# Power.net
KiCad netlist of a schematic drawn in Altium Designer
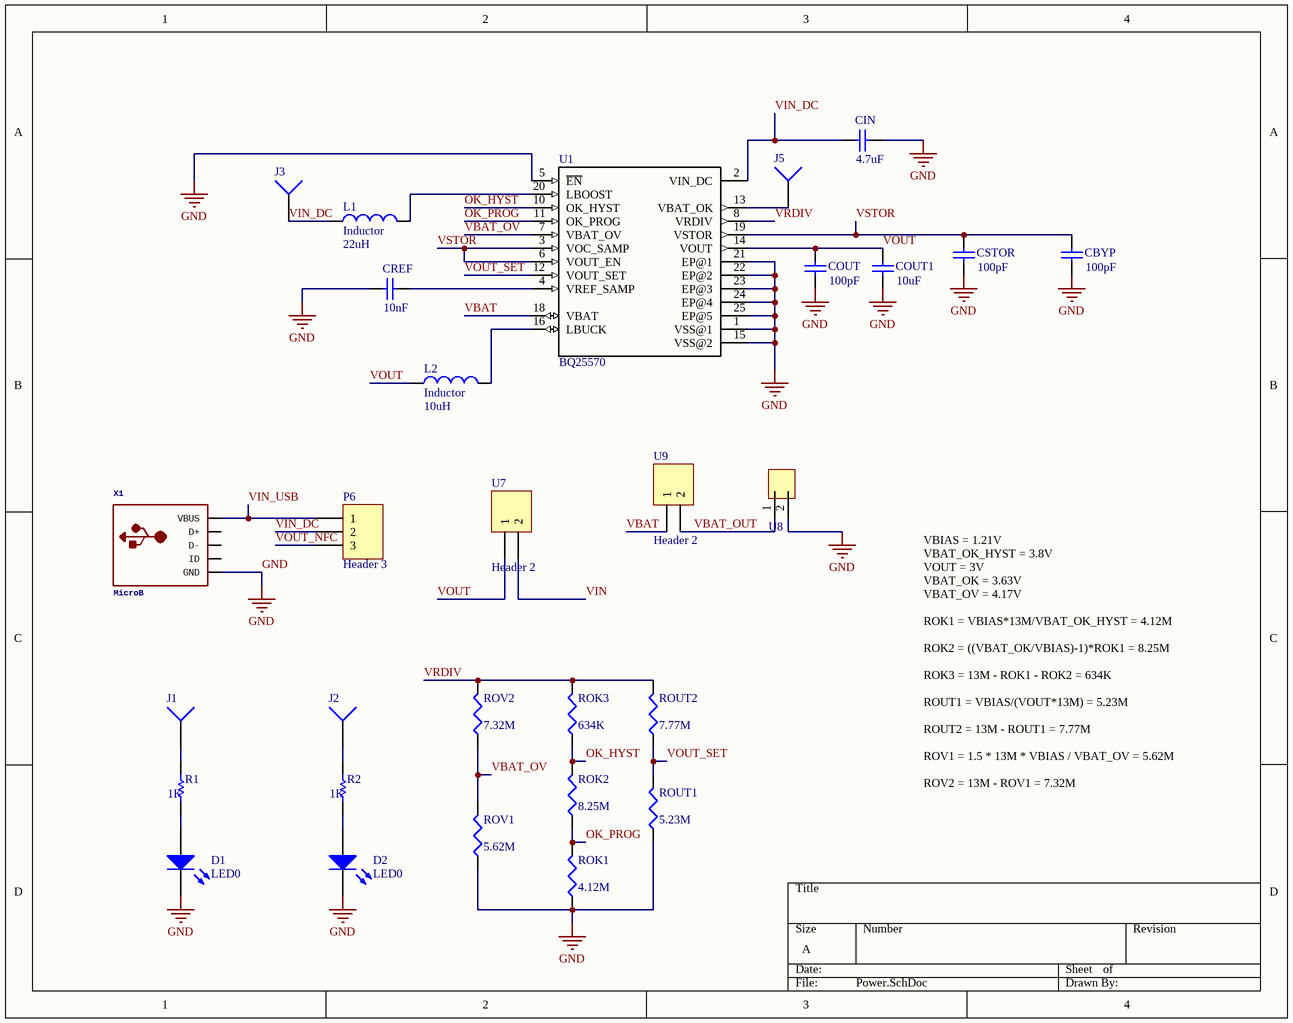
[diagram p0: Power.SchDoc]

(export (version "E")
  (design (tool "Eeschema 10.0.6"))
  (components
    (comp (ref "CBYP")
      (value "100pF")
      (footprint "C1206")
      (description "CAP CER 100PF 50V C0G/NPO 0603")
      (fields (field (name "DIGI-KEY PART NUMBER") "311-1069-1-ND") (field (name "MANUFACTURER") "Yageo"))
      (libsource (lib "Miscellaneous Devices") (part "Cap Semi"))
    )
    (comp (ref "CIN")
      (value "4.7uF")
      (footprint "C1206")
      (description "CAP CER 4.7UF 10V X5R 0603")
      (fields
        (field (name "DIGI-KEY PART NUMBER") "1276-6684-1-ND")
        (field (name "MANUFACTURER") "Samsung Electro-Mechanics")
      )
      (libsource (lib "Miscellaneous Devices") (part "Cap Semi"))
    )
    (comp (ref "COUT")
      (value "100pF")
      (footprint "C1206")
      (description "CAP CER 100PF 50V C0G/NPO 0603")
      (fields (field (name "DIGI-KEY PART NUMBER") "311-1069-1-ND") (field (name "MANUFACTURER") "Yageo"))
      (libsource (lib "Miscellaneous Devices") (part "Cap Semi"))
    )
    (comp (ref "COUT1")
      (value "10uF")
      (footprint "C1206")
      (description "CL10A106MQ8NNNC")
      (fields
        (field (name "DIGI-KEY PART NUMBER") "1276-1119-1-ND")
        (field (name "MANUFACTURER") "Samsung Electro-Mechanics")
      )
      (libsource (lib "Miscellaneous Devices") (part "Cap Semi"))
    )
    (comp (ref "CREF")
      (value "10nF")
      (footprint "C1206")
      (description "CAP CER 10000PF 100V X7R 0603")
      (fields
        (field (name "DIGI-KEY PART NUMBER") "445-1305-1-ND")
        (field (name "MANUFACTURER") "TDK Corporation")
      )
      (libsource (lib "Miscellaneous Devices") (part "Cap Semi"))
    )
    (comp (ref "CSTOR")
      (value "100pF")
      (footprint "C1206")
      (description "CAP CER 100PF 50V C0G/NPO 0603")
      (fields (field (name "DIGI-KEY PART NUMBER") "311-1069-1-ND") (field (name "MANUFACTURER") "Yageo"))
      (libsource (lib "Miscellaneous Devices") (part "Cap Semi"))
    )
    (comp (ref "D1")
      (value "LED0")
      (footprint "LED-0")
      (description "LED BLUE CLEAR CHIP SMD")
      (fields
        (field (name "DIGI-KEY PART NUMBER") "754-1434-1-ND")
        (field (name "MANUFACTURER") "Kingbright")
      )
      (libsource (lib "Miscellaneous Devices") (part "LED0"))
    )
    (comp (ref "D2")
      (value "LED0")
      (footprint "LED-0")
      (description "LED BLUE CLEAR CHIP SMD")
      (fields
        (field (name "DIGI-KEY PART NUMBER") "754-1434-1-ND")
        (field (name "MANUFACTURER") "Kingbright")
      )
      (libsource (lib "Miscellaneous Devices") (part "LED0"))
    )
    (comp (ref "J1")
      (value "Socket")
      (footprint "PIN1")
      (fields (field (name "PUBLISHER") "Altium Limited"))
      (libsource (lib "Miscellaneous Connectors") (part "Socket"))
    )
    (comp (ref "J2")
      (value "Socket")
      (footprint "PIN1")
      (fields (field (name "PUBLISHER") "Altium Limited"))
      (libsource (lib "Miscellaneous Connectors") (part "Socket"))
    )
    (comp (ref "J3")
      (value "Socket")
      (footprint "PIN1")
      (fields (field (name "PUBLISHER") "Altium Limited"))
      (libsource (lib "Miscellaneous Connectors") (part "Socket"))
    )
    (comp (ref "J5")
      (value "Socket")
      (footprint "PIN1")
      (fields (field (name "PUBLISHER") "Altium Limited"))
      (libsource (lib "Miscellaneous Connectors") (part "Socket"))
    )
    (comp (ref "L1")
      (value "Inductor")
      (footprint "0402-A")
      (description "FIXED IND 22UH 510MA 450 MOHM")
      (fields
        (field (name "ALTIUM_VALUE") "22uH")
        (field (name "DIGI-KEY PART NUMBER") "732-1012-1-ND")
        (field (name "MANUFACTURER") "Wurth Electronics Inc.")
      )
      (libsource (lib "Miscellaneous Devices") (part "Inductor"))
    )
    (comp (ref "L2")
      (value "Inductor")
      (footprint "0402-A")
      (description "FIXED IND 10UH 1A 460 MOHM SMD")
      (fields
        (field (name "ALTIUM_VALUE") "10uH")
        (field (name "DIGI-KEY PART NUMBER") "490-10563-1-ND")
        (field (name "MANUFACTURER") "Murata Electronics North America")
      )
      (libsource (lib "Miscellaneous Devices") (part "Inductor"))
    )
    (comp (ref "P6")
      (value "Header 3")
      (footprint "HDR1X3")
      (description "Header, 3-Pin")
      (fields (field (name "PUBLISHER") "Altium Limited"))
      (libsource (lib "Miscellaneous Connectors") (part "Header 3"))
    )
    (comp (ref "R1")
      (value "1K")
      (footprint "AXIAL-0.3")
      (description "RES SMD 1K OHM 0.5% 1/16W 0603")
      (fields (field (name "DIGI-KEY PART NUMBER") "RR08P1.0KDCT-ND") (field (name "MANUFACTURER") "Susumu"))
      (libsource (lib "Miscellaneous Devices") (part "Res1"))
    )
    (comp (ref "R2")
      (value "1K")
      (footprint "AXIAL-0.3")
      (description "RES SMD 1K OHM 0.5% 1/16W 0603")
      (fields (field (name "DIGI-KEY PART NUMBER") "RR08P1.0KDCT-ND") (field (name "MANUFACTURER") "Susumu"))
      (libsource (lib "Miscellaneous Devices") (part "Res1"))
    )
    (comp (ref "ROK1")
      (value "4.12M")
      (footprint "J1-0603")
      (description "RES SMD 4.12M OHM 1% 1/10W 0603")
      (fields
        (field (name "DIGI-KEY PART NUMBER") "541-4.12MHCT-ND")
        (field (name "MANUFACTURER PART NUMBER") "CRCW06034M12FKEA")
      )
      (libsource (lib "Miscellaneous Devices") (part "Res3"))
    )
    (comp (ref "ROK2")
      (value "8.25M")
      (footprint "J1-0603")
      (description "RES SMD 8.25M OHM 1% 1/10W 0603")
      (fields
        (field (name "DIGI-KEY PART NUMBER") "541-8.25MHCT-ND")
        (field (name "MANUFACTURER") "Vishay Dale")
      )
      (libsource (lib "Miscellaneous Devices") (part "Res3"))
    )
    (comp (ref "ROK3")
      (value "634K")
      (footprint "J1-0603")
      (description "RES SMD 634K OHM 1% 1/10W 0603")
      (fields (field (name "DIGI-KEY PART NUMBER") "311-634KHRCT-ND") (field (name "MANUFACTURER") "Yageo"))
      (libsource (lib "Miscellaneous Devices") (part "Res3"))
    )
    (comp (ref "ROUT1")
      (value "5.23M")
      (footprint "J1-0603")
      (description "RES SMD 5.23M OHM 1% 1/10W 0603")
      (fields
        (field (name "DIGI-KEY PART NUMBER") "541-5.23MHCT-ND")
        (field (name "MANUFACTURER") "Vishay Dale")
      )
      (libsource (lib "Miscellaneous Devices") (part "Res3"))
    )
    (comp (ref "ROUT2")
      (value "7.77M")
      (footprint "J1-0603")
      (description "RES SMD 7.68M OHM 1% 1/10W 0603")
      (fields
        (field (name "DIGI-KEY PART NUMBER") "541-7.68MHCT-ND")
        (field (name "MANUFACTURER") "Vishay Dale")
      )
      (libsource (lib "Miscellaneous Devices") (part "Res3"))
    )
    (comp (ref "ROV1")
      (value "5.62M")
      (footprint "J1-0603")
      (description "RES 5.62M OHM 1% 1/10W 0603")
      (fields
        (field (name "DIGI-KEY PART NUMBER") "RMCF0603FT5M62CT-ND")
        (field (name "MANUFACTURER") "Stackpole Electronics Inc.")
      )
      (libsource (lib "Miscellaneous Devices") (part "Res3"))
    )
    (comp (ref "ROV2")
      (value "7.32M")
      (footprint "J1-0603")
      (description "RES 7.32M OHM 1% 1/10W 0603")
      (fields
        (field (name "DIGI-KEY PART NUMBER") "RMCF0603FT7M32CT-ND")
        (field (name "MANUFACTURER") "Stackpole Electronics Inc.")
      )
      (libsource (lib "Miscellaneous Devices") (part "Res3"))
    )
    (comp (ref "U1")
      (value "BQ25570")
      (footprint "QFN50P350X350X100-21N")
      (description "IC ENERGY HARV CTRLR BATT 20VQFN")
      (fields
        (field (name "DIGI-KEY PART NUMBER") "296-39934-1-ND")
        (field (name "MANUFACTURER") "Texas Instruments")
      )
      (libsource (lib "phone_cover_parts") (part "BQ25570RGRR"))
    )
    (comp (ref "U7")
      (value "Header 2")
      (footprint "HDR1X2")
      (description "Header, 2-Pin")
      (fields (field (name "PUBLISHER") "Altium Limited"))
      (libsource (lib "Miscellaneous Connectors") (part "Header 2"))
    )
    (comp (ref "U8")
      (value "JST_Conn")
      (footprint "JST")
      (libsource (lib "EFM32PG12B500F1024GM48") (part "JST_Conn"))
    )
    (comp (ref "U9")
      (value "Header 2")
      (footprint "HDR1X2")
      (description "Header, 2-Pin")
      (fields (field (name "PUBLISHER") "Altium Limited"))
      (libsource (lib "Miscellaneous Connectors") (part "Header 2"))
    )
    (comp (ref "X1")
      (value "MicroB")
      (footprint "629105150921")
      (description "CONN RCPT STD MICRO USB TYPE B")
      (fields
        (field (name "MANUFACTURER") "Amphenol FCI")
        (field (name "MANUFACTURERPARTNO") "10103594-0001LF")
      )
      (libsource (lib "SherLock_SchLib") (part "USBMICRO_20329"))
    )
  )
  (nets
    (net (code "1") (name "/OK_HYST") (class "Default")
      (node (ref "ROK2") (pin "2") (pinfunction "2_2") (pintype "passive"))
      (node (ref "ROK3") (pin "1") (pinfunction "1_1") (pintype "passive"))
      (node (ref "U1") (pin "10") (pinfunction "OK_HYST_10") (pintype "input"))
    )
    (net (code "2") (name "/OK_PROG") (class "Default")
      (node (ref "ROK1") (pin "2") (pinfunction "2_2") (pintype "passive"))
      (node (ref "ROK2") (pin "1") (pinfunction "1_1") (pintype "passive"))
      (node (ref "U1") (pin "11") (pinfunction "OK_PROG_11") (pintype "input"))
    )
    (net (code "3") (name "/VBAT") (class "Default")
      (node (ref "U1") (pin "18") (pinfunction "VBAT_18") (pintype "bidirectional"))
      (node (ref "U9") (pin "1") (pinfunction "1_1") (pintype "passive"))
    )
    (net (code "4") (name "/VBAT_OUT") (class "Default")
      (node (ref "U8") (pin "1") (pinfunction "1_1") (pintype "passive"))
      (node (ref "U9") (pin "2") (pinfunction "2_2") (pintype "passive"))
    )
    (net (code "5") (name "/VBAT_OV") (class "Default")
      (node (ref "ROV1") (pin "2") (pinfunction "2_2") (pintype "passive"))
      (node (ref "ROV2") (pin "1") (pinfunction "1_1") (pintype "passive"))
      (node (ref "U1") (pin "7") (pinfunction "VBAT_OV_7") (pintype "input"))
    )
    (net (code "6") (name "/VIN") (class "Default")
      (node (ref "U7") (pin "2") (pinfunction "2_2") (pintype "passive"))
    )
    (net (code "7") (name "/VIN_DC") (class "Default")
      (node (ref "CIN") (pin "1") (pinfunction "1_1") (pintype "passive"))
      (node (ref "J3") (pin "1") (pinfunction "1_1") (pintype "passive"))
      (node (ref "L1") (pin "1") (pinfunction "1_1") (pintype "passive"))
      (node (ref "P6") (pin "2") (pinfunction "2_2") (pintype "passive"))
      (node (ref "U1") (pin "2") (pinfunction "VIN_DC_2") (pintype "power_in"))
    )
    (net (code "8") (name "/VIN_USB") (class "Default")
      (node (ref "P6") (pin "1") (pinfunction "1_1") (pintype "passive"))
      (node (ref "X1") (pin "1") (pinfunction "VBUS_1") (pintype "power_in"))
    )
    (net (code "9") (name "/VOUT") (class "Default")
      (node (ref "COUT") (pin "2") (pinfunction "2_2") (pintype "passive"))
      (node (ref "COUT1") (pin "2") (pinfunction "2_2") (pintype "passive"))
      (node (ref "L2") (pin "1") (pinfunction "1_1") (pintype "passive"))
      (node (ref "U1") (pin "14") (pinfunction "VOUT_14") (pintype "output"))
      (node (ref "U7") (pin "1") (pinfunction "1_1") (pintype "passive"))
    )
    (net (code "10") (name "/VOUT_NFC") (class "Default")
      (node (ref "P6") (pin "3") (pinfunction "3_3") (pintype "passive"))
    )
    (net (code "11") (name "/VOUT_SET") (class "Default")
      (node (ref "ROUT1") (pin "2") (pinfunction "2_2") (pintype "passive"))
      (node (ref "ROUT2") (pin "1") (pinfunction "1_1") (pintype "passive"))
      (node (ref "U1") (pin "12") (pinfunction "VOUT_SET_12") (pintype "input"))
    )
    (net (code "12") (name "/VRDIV") (class "Default")
      (node (ref "ROK3") (pin "2") (pinfunction "2_2") (pintype "passive"))
      (node (ref "ROUT2") (pin "2") (pinfunction "2_2") (pintype "passive"))
      (node (ref "ROV2") (pin "2") (pinfunction "2_2") (pintype "passive"))
      (node (ref "U1") (pin "8") (pinfunction "VRDIV_8") (pintype "output"))
    )
    (net (code "13") (name "/VSTOR") (class "Default")
      (node (ref "CBYP") (pin "2") (pinfunction "2_2") (pintype "passive"))
      (node (ref "CSTOR") (pin "2") (pinfunction "2_2") (pintype "passive"))
      (node (ref "U1") (pin "19") (pinfunction "VSTOR_19") (pintype "output"))
      (node (ref "U1") (pin "3") (pinfunction "VOC_SAMP_3") (pintype "input"))
      (node (ref "U1") (pin "6") (pinfunction "VOUT_EN_6") (pintype "input"))
    )
    (net (code "14") (name "GND") (class "Default")
      (node (ref "CBYP") (pin "1") (pinfunction "1_1") (pintype "passive"))
      (node (ref "CIN") (pin "2") (pinfunction "2_2") (pintype "passive"))
      (node (ref "COUT") (pin "1") (pinfunction "1_1") (pintype "passive"))
      (node (ref "COUT1") (pin "1") (pinfunction "1_1") (pintype "passive"))
      (node (ref "CREF") (pin "1") (pinfunction "1_1") (pintype "passive"))
      (node (ref "CSTOR") (pin "1") (pinfunction "1_1") (pintype "passive"))
      (node (ref "D1") (pin "2") (pinfunction "K_2") (pintype "passive"))
      (node (ref "D2") (pin "2") (pinfunction "K_2") (pintype "passive"))
      (node (ref "ROK1") (pin "1") (pinfunction "1_1") (pintype "passive"))
      (node (ref "ROUT1") (pin "1") (pinfunction "1_1") (pintype "passive"))
      (node (ref "ROV1") (pin "1") (pinfunction "1_1") (pintype "passive"))
      (node (ref "U1") (pin "1") (pinfunction "VSS@1_1") (pintype "power_in"))
      (node (ref "U1") (pin "15") (pinfunction "VSS@2_15") (pintype "power_in"))
      (node (ref "U1") (pin "21") (pinfunction "EP@1_21") (pintype "power_in"))
      (node (ref "U1") (pin "22") (pinfunction "EP@2_22") (pintype "power_in"))
      (node (ref "U1") (pin "23") (pinfunction "EP@3_23") (pintype "power_in"))
      (node (ref "U1") (pin "24") (pinfunction "EP@4_24") (pintype "power_in"))
      (node (ref "U1") (pin "25") (pinfunction "EP@5_25") (pintype "power_in"))
      (node (ref "U1") (pin "5") (pinfunction "~{EN}_5") (pintype "input"))
      (node (ref "U8") (pin "2") (pinfunction "2_2") (pintype "passive"))
      (node (ref "X1") (pin "5") (pinfunction "GND_5") (pintype "power_in"))
    )
    (net (code "15") (name "Net-(D1-A)") (class "Default")
      (node (ref "D1") (pin "1") (pinfunction "A_1") (pintype "passive"))
      (node (ref "R1") (pin "1") (pinfunction "1_1") (pintype "passive"))
    )
    (net (code "16") (name "Net-(D2-A)") (class "Default")
      (node (ref "D2") (pin "1") (pinfunction "A_1") (pintype "passive"))
      (node (ref "R2") (pin "1") (pinfunction "1_1") (pintype "passive"))
    )
    (net (code "17") (name "Net-(J1-Pad1)") (class "Default")
      (node (ref "J1") (pin "1") (pinfunction "1_1") (pintype "passive"))
      (node (ref "R1") (pin "2") (pinfunction "2_2") (pintype "passive"))
    )
    (net (code "18") (name "Net-(J2-Pad1)") (class "Default")
      (node (ref "J2") (pin "1") (pinfunction "1_1") (pintype "passive"))
      (node (ref "R2") (pin "2") (pinfunction "2_2") (pintype "passive"))
    )
    (net (code "19") (name "Net-(U1-LBOOST)") (class "Default")
      (node (ref "L1") (pin "2") (pinfunction "2_2") (pintype "passive"))
      (node (ref "U1") (pin "20") (pinfunction "LBOOST_20") (pintype "input"))
    )
    (net (code "20") (name "Net-(U1-LBUCK)") (class "Default")
      (node (ref "L2") (pin "2") (pinfunction "2_2") (pintype "passive"))
      (node (ref "U1") (pin "16") (pinfunction "LBUCK_16") (pintype "bidirectional"))
    )
    (net (code "21") (name "Net-(U1-VBAT_OK)") (class "Default")
      (node (ref "J5") (pin "1") (pinfunction "1_1") (pintype "passive"))
      (node (ref "U1") (pin "13") (pinfunction "VBAT_OK_13") (pintype "output"))
    )
    (net (code "22") (name "Net-(U1-VREF_SAMP)") (class "Default")
      (node (ref "CREF") (pin "2") (pinfunction "2_2") (pintype "passive"))
      (node (ref "U1") (pin "4") (pinfunction "VREF_SAMP_4") (pintype "input"))
    )
    (net (code "23") (name "unconnected-(X1-D+-Pad2)") (class "Default")
      (node (ref "X1") (pin "2") (pinfunction "D+_2") (pintype "passive"))
    )
    (net (code "24") (name "unconnected-(X1-D--Pad3)") (class "Default")
      (node (ref "X1") (pin "3") (pinfunction "D-_3") (pintype "passive"))
    )
    (net (code "25") (name "unconnected-(X1-ID-Pad4)") (class "Default")
      (node (ref "X1") (pin "4") (pinfunction "ID_4") (pintype "passive"))
    )
  )
)
